# IMU_Unit.net
KiCad netlist of a schematic drawn in Altium Designer
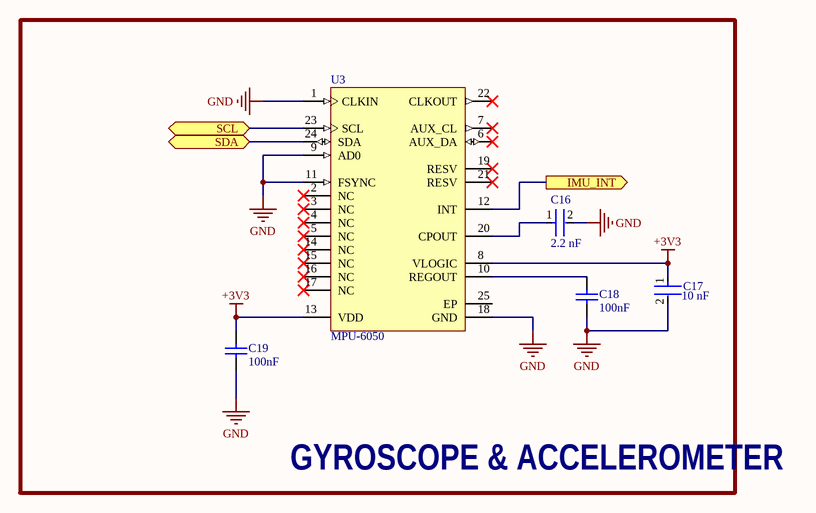
[diagram p0: IMU Unit.SchDoc]

(export (version "E")
  (design (tool "Eeschema 10.0.6"))
  (components
    (comp (ref "C16")
      (value "CC0402KRX7R9BB222")
      (footprint "FP-CC0402-MFG")
      (description "CAP CER 2200PF 50V X7R 0402")
      (fields
        (field (name "TOLERANCE") "0.1")
        (field (name "OCTOPART") "https://octopart.com/cc0402krx7r9bb222-yageo-39467642")
        (field (name "CAPACITANCE") "2.2 nF")
      )
      (libsource (lib "Altium Content Vault") (part "11868f565c42a9108669ba33697ecf6"))
    )
    (comp (ref "C17")
      (value "CC0402KRX7R9BB103")
      (footprint "FP-CC0402-MFG")
      (description "CAP CER 10000PF 50V X7R 0402")
      (fields
        (field (name "OCTOPART") "https://octopart.com/cc0402krx7r9bb103-yageo-8376513")
        (field (name "CAPACITANCE") "10 nF")
        (field (name "MANUFACTURER") "YAGEO")
      )
      (libsource (lib "Altium Content Vault") (part "11868f565c42a9108669ba33697ecf6"))
    )
    (comp (ref "C18")
      (value "CL05B104KO5NNNC")
      (footprint "CAPC1050X55X23ML05T13")
      (description "Chip Capacitor, 100 nF, +/- 10%, 16 V, -55 to 125 degC, 0402 (1005 Metric), RoHS, Tape and Reel")
      (fields (field (name "MANUFACTURER") "Samsung Electro-Mechanics") (field (name "CAPACITANCE") "100nF"))
      (libsource (lib "Altium Content Vault") (part "CAP-NP-2"))
    )
    (comp (ref "C19")
      (value "CL05B104KO5NNNC")
      (footprint "CAPC1050X55X23ML05T13")
      (description "Chip Capacitor, 100 nF, +/- 10%, 16 V, -55 to 125 degC, 0402 (1005 Metric), RoHS, Tape and Reel")
      (fields (field (name "MANUFACTURER") "Samsung Electro-Mechanics") (field (name "CAPACITANCE") "100nF"))
      (libsource (lib "Altium Content Vault") (part "CAP-NP-2"))
    )
    (comp (ref "U3")
      (value "MPU-6050")
      (footprint "IS-QFN-24_V")
      (fields (field (name "MANUFACTURER") "InvenSense"))
      (libsource (lib "Altium Content Vault") (part "IS-MPU-6050-QFN-24"))
    )
  )
  (nets
    (net (code "1") (name "+3V3") (class "Default")
      (node (ref "C17") (pin "1") (pinfunction "1_1") (pintype "passive"))
      (node (ref "C19") (pin "2") (pinfunction "2_2") (pintype "passive"))
      (node (ref "U3") (pin "13") (pinfunction "VDD_13") (pintype "power_in"))
      (node (ref "U3") (pin "8") (pinfunction "VLOGIC_8") (pintype "power_in"))
    )
    (net (code "2") (name "/IMU_INT") (class "Default")
      (node (ref "U3") (pin "12") (pinfunction "INT_12") (pintype "open_collector"))
    )
    (net (code "3") (name "/SCL") (class "Default")
      (node (ref "U3") (pin "23") (pinfunction "SCL_23") (pintype "input"))
    )
    (net (code "4") (name "/SDA") (class "Default")
      (node (ref "U3") (pin "24") (pinfunction "SDA_24") (pintype "bidirectional"))
    )
    (net (code "5") (name "GND") (class "Default")
      (node (ref "C16") (pin "2") (pinfunction "2_2") (pintype "passive"))
      (node (ref "C17") (pin "2") (pinfunction "2_2") (pintype "passive"))
      (node (ref "C18") (pin "1") (pinfunction "1_1") (pintype "passive"))
      (node (ref "C19") (pin "1") (pinfunction "1_1") (pintype "passive"))
      (node (ref "U3") (pin "1") (pinfunction "CLKIN_1") (pintype "input"))
      (node (ref "U3") (pin "11") (pinfunction "FSYNC_11") (pintype "input"))
      (node (ref "U3") (pin "18") (pinfunction "GND_18") (pintype "power_in"))
      (node (ref "U3") (pin "9") (pinfunction "AD0_9") (pintype "input"))
    )
    (net (code "6") (name "Net-(U3-CPOUT)") (class "Default")
      (node (ref "C16") (pin "1") (pinfunction "1_1") (pintype "passive"))
      (node (ref "U3") (pin "20") (pinfunction "CPOUT_20") (pintype "passive"))
    )
    (net (code "7") (name "Net-(U3-REGOUT)") (class "Default")
      (node (ref "C18") (pin "2") (pinfunction "2_2") (pintype "passive"))
      (node (ref "U3") (pin "10") (pinfunction "REGOUT_10") (pintype "passive"))
    )
    (net (code "8") (name "unconnected-(U3-AUX_CL-Pad7)") (class "Default")
      (node (ref "U3") (pin "7") (pinfunction "AUX_CL_7") (pintype "output+no_connect"))
    )
    (net (code "9") (name "unconnected-(U3-AUX_DA-Pad6)") (class "Default")
      (node (ref "U3") (pin "6") (pinfunction "AUX_DA_6") (pintype "bidirectional+no_connect"))
    )
    (net (code "10") (name "unconnected-(U3-CLKOUT-Pad22)") (class "Default")
      (node (ref "U3") (pin "22") (pinfunction "CLKOUT_22") (pintype "output+no_connect"))
    )
    (net (code "11") (name "unconnected-(U3-EP-Pad25)") (class "Default")
      (node (ref "U3") (pin "25") (pinfunction "EP_25") (pintype "power_in"))
    )
    (net (code "12") (name "unconnected-(U3-NC-Pad2)") (class "Default")
      (node (ref "U3") (pin "2") (pinfunction "NC_2") (pintype "passive+no_connect"))
    )
    (net (code "13") (name "unconnected-(U3-NC-Pad3)") (class "Default")
      (node (ref "U3") (pin "3") (pinfunction "NC_3") (pintype "passive+no_connect"))
    )
    (net (code "14") (name "unconnected-(U3-NC-Pad4)") (class "Default")
      (node (ref "U3") (pin "4") (pinfunction "NC_4") (pintype "passive+no_connect"))
    )
    (net (code "15") (name "unconnected-(U3-NC-Pad5)") (class "Default")
      (node (ref "U3") (pin "5") (pinfunction "NC_5") (pintype "passive+no_connect"))
    )
    (net (code "16") (name "unconnected-(U3-NC-Pad14)") (class "Default")
      (node (ref "U3") (pin "14") (pinfunction "NC_14") (pintype "passive+no_connect"))
    )
    (net (code "17") (name "unconnected-(U3-NC-Pad15)") (class "Default")
      (node (ref "U3") (pin "15") (pinfunction "NC_15") (pintype "passive+no_connect"))
    )
    (net (code "18") (name "unconnected-(U3-NC-Pad16)") (class "Default")
      (node (ref "U3") (pin "16") (pinfunction "NC_16") (pintype "passive+no_connect"))
    )
    (net (code "19") (name "unconnected-(U3-NC-Pad17)") (class "Default")
      (node (ref "U3") (pin "17") (pinfunction "NC_17") (pintype "passive+no_connect"))
    )
    (net (code "20") (name "unconnected-(U3-RESV-Pad19)") (class "Default")
      (node (ref "U3") (pin "19") (pinfunction "RESV_19") (pintype "passive+no_connect"))
    )
    (net (code "21") (name "unconnected-(U3-RESV-Pad21)") (class "Default")
      (node (ref "U3") (pin "21") (pinfunction "RESV_21") (pintype "passive+no_connect"))
    )
  )
)
